# d101-lofi-delay.net
KiCad netlist of a schematic drawn in EAGLE
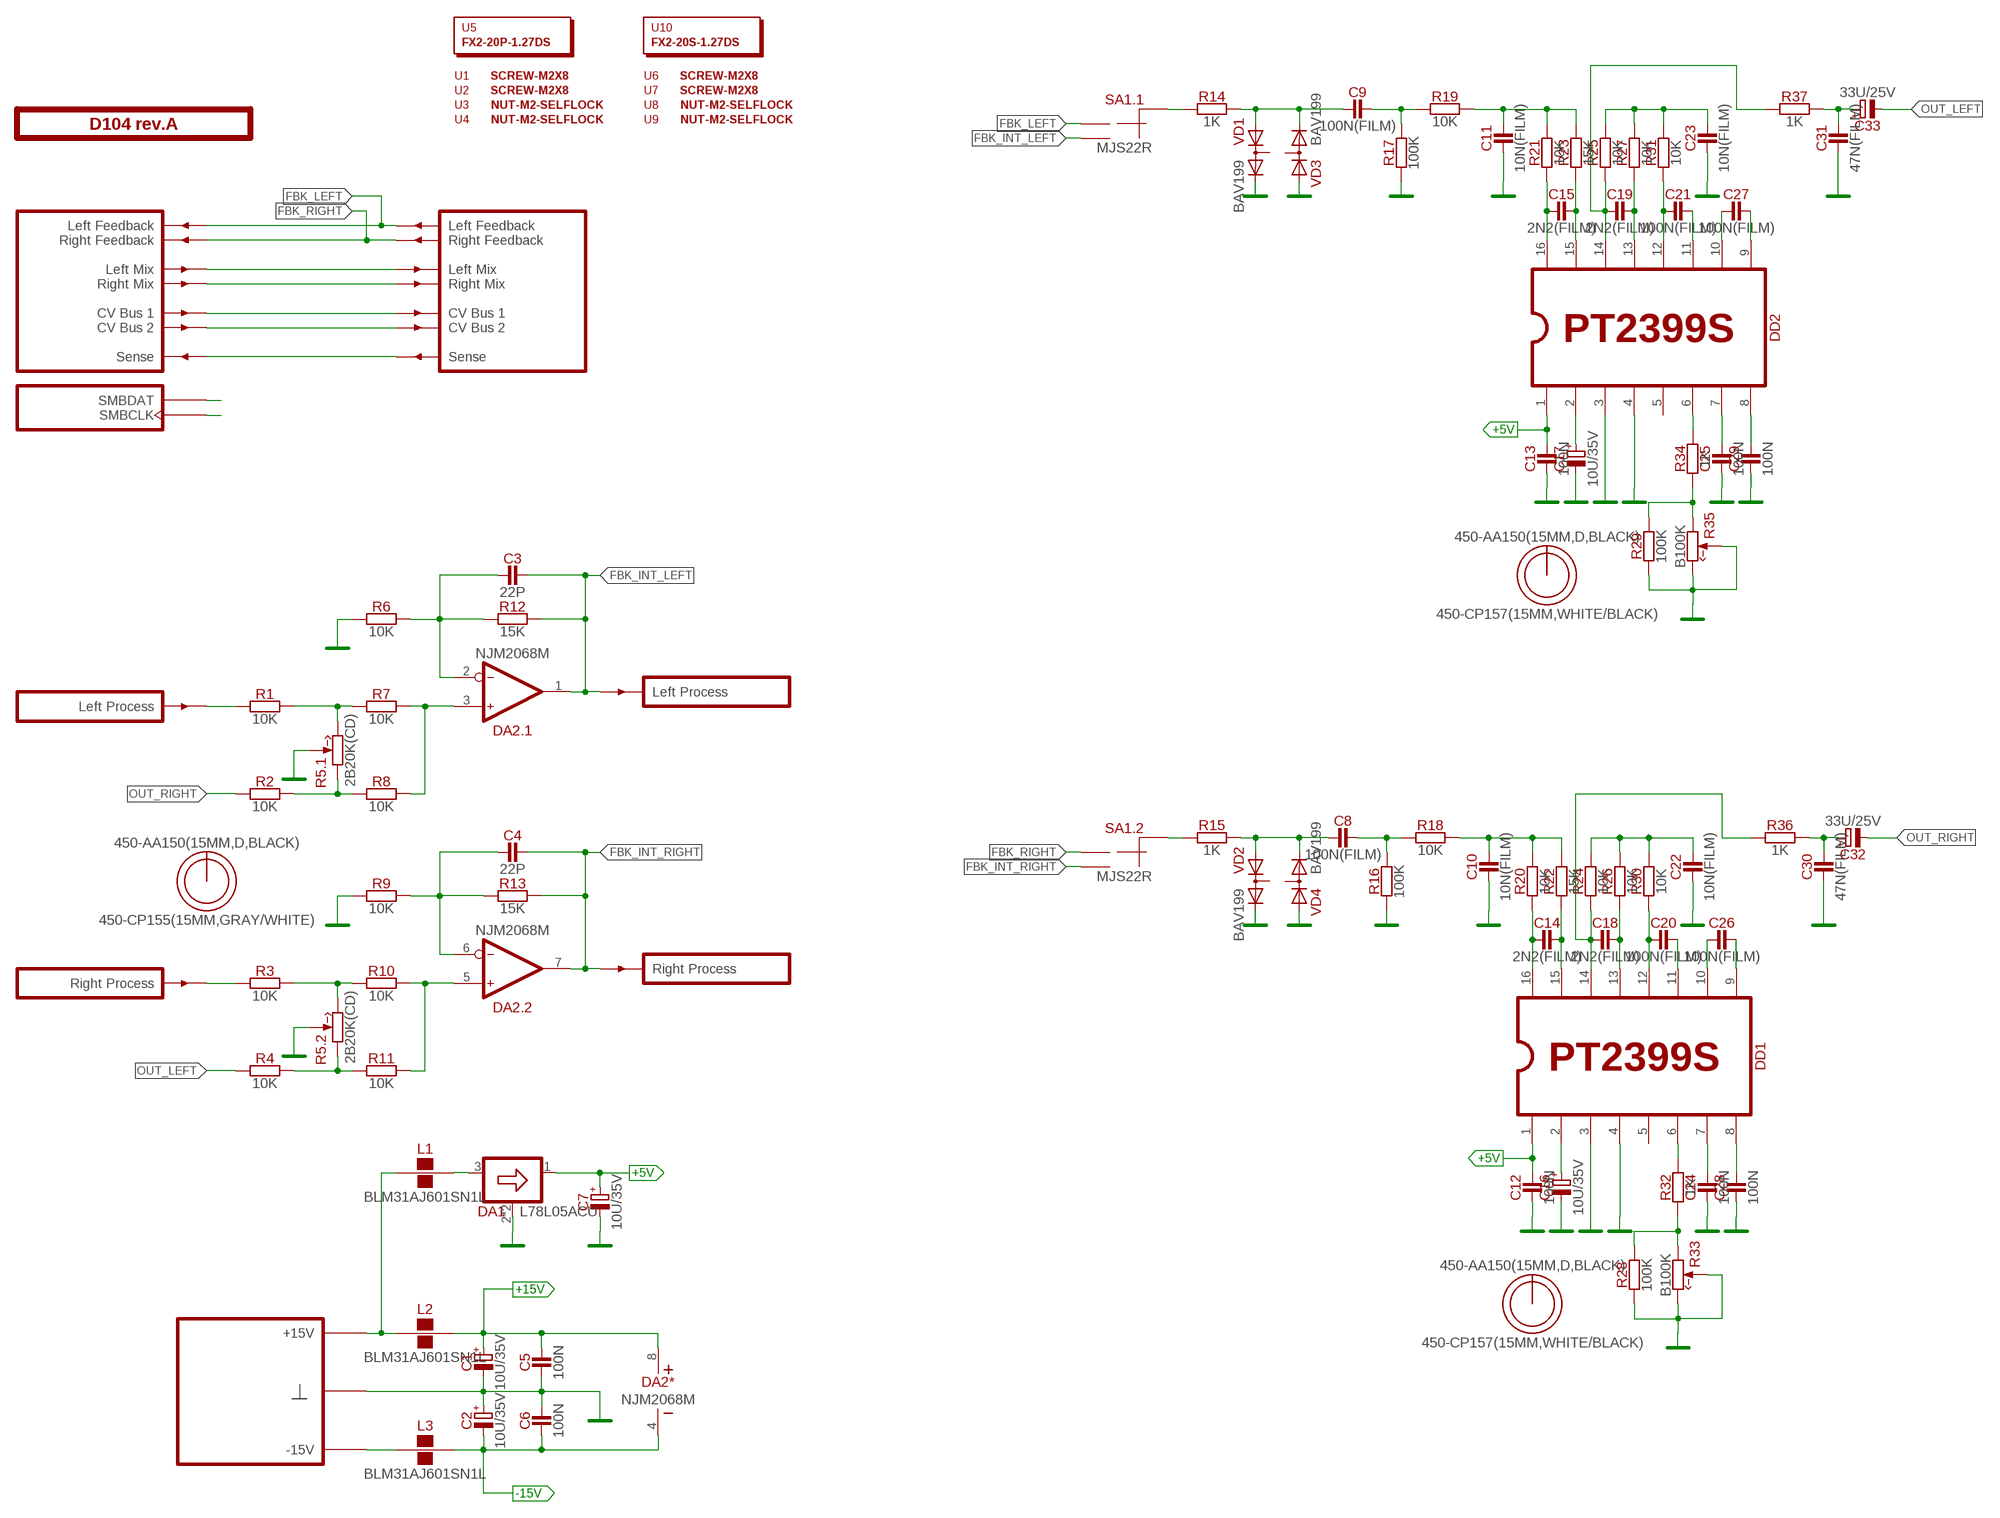
[diagram p0: schematic, sheet 1]

(export (version "E")
  (design (tool "Eeschema 10.0.6"))
  (components
    (comp (ref "C1")
      (value "10U/35V")
      (footprint "eagle-import:E2-5")
      (libsource (lib "eagle-import") (part "?10U/35V"))
    )
    (comp (ref "C2")
      (value "10U/35V")
      (footprint "eagle-import:E2-5")
      (libsource (lib "eagle-import") (part "?10U/35V"))
    )
    (comp (ref "C3")
      (value "22P")
      (footprint "eagle-import:C-0805")
      (libsource (lib "eagle-import") (part "?22P"))
    )
    (comp (ref "C4")
      (value "22P")
      (footprint "eagle-import:C-0805")
      (libsource (lib "eagle-import") (part "?22P"))
    )
    (comp (ref "C5")
      (value "100N")
      (footprint "eagle-import:C-0805")
      (libsource (lib "eagle-import") (part "?100N"))
    )
    (comp (ref "C6")
      (value "100N")
      (footprint "eagle-import:C-0805")
      (libsource (lib "eagle-import") (part "?100N"))
    )
    (comp (ref "C7")
      (value "10U/35V")
      (footprint "eagle-import:E2-5")
      (libsource (lib "eagle-import") (part "?10U/35V"))
    )
    (comp (ref "C8")
      (value "100N(FILM)")
      (footprint "eagle-import:C050-025X075")
      (libsource (lib "eagle-import") (part "?100N(FILM)"))
    )
    (comp (ref "C9")
      (value "100N(FILM)")
      (footprint "eagle-import:C050-025X075")
      (libsource (lib "eagle-import") (part "?100N(FILM)"))
    )
    (comp (ref "C10")
      (value "10N(FILM)")
      (footprint "eagle-import:C050-025X075")
      (libsource (lib "eagle-import") (part "?10N(FILM)"))
    )
    (comp (ref "C11")
      (value "10N(FILM)")
      (footprint "eagle-import:C050-025X075")
      (libsource (lib "eagle-import") (part "?10N(FILM)"))
    )
    (comp (ref "C12")
      (value "100N")
      (footprint "eagle-import:C-0805")
      (libsource (lib "eagle-import") (part "?100N"))
    )
    (comp (ref "C13")
      (value "100N")
      (footprint "eagle-import:C-0805")
      (libsource (lib "eagle-import") (part "?100N"))
    )
    (comp (ref "C14")
      (value "2N2(FILM)")
      (footprint "eagle-import:C050-025X075")
      (libsource (lib "eagle-import") (part "?2N2(FILM)"))
    )
    (comp (ref "C15")
      (value "2N2(FILM)")
      (footprint "eagle-import:C050-025X075")
      (libsource (lib "eagle-import") (part "?2N2(FILM)"))
    )
    (comp (ref "C16")
      (value "10U/35V")
      (footprint "eagle-import:E2-5")
      (libsource (lib "eagle-import") (part "?10U/35V"))
    )
    (comp (ref "C17")
      (value "10U/35V")
      (footprint "eagle-import:E2-5")
      (libsource (lib "eagle-import") (part "?10U/35V"))
    )
    (comp (ref "C18")
      (value "2N2(FILM)")
      (footprint "eagle-import:C050-025X075")
      (libsource (lib "eagle-import") (part "?2N2(FILM)"))
    )
    (comp (ref "C19")
      (value "2N2(FILM)")
      (footprint "eagle-import:C050-025X075")
      (libsource (lib "eagle-import") (part "?2N2(FILM)"))
    )
    (comp (ref "C20")
      (value "100N(FILM)")
      (footprint "eagle-import:C050-025X075")
      (libsource (lib "eagle-import") (part "?100N(FILM)"))
    )
    (comp (ref "C21")
      (value "100N(FILM)")
      (footprint "eagle-import:C050-025X075")
      (libsource (lib "eagle-import") (part "?100N(FILM)"))
    )
    (comp (ref "C22")
      (value "10N(FILM)")
      (footprint "eagle-import:C050-025X075")
      (libsource (lib "eagle-import") (part "?10N(FILM)"))
    )
    (comp (ref "C23")
      (value "10N(FILM)")
      (footprint "eagle-import:C050-025X075")
      (libsource (lib "eagle-import") (part "?10N(FILM)"))
    )
    (comp (ref "C24")
      (value "100N")
      (footprint "eagle-import:C-0805")
      (libsource (lib "eagle-import") (part "?100N"))
    )
    (comp (ref "C25")
      (value "100N")
      (footprint "eagle-import:C-0805")
      (libsource (lib "eagle-import") (part "?100N"))
    )
    (comp (ref "C26")
      (value "100N(FILM)")
      (footprint "eagle-import:C050-025X075")
      (libsource (lib "eagle-import") (part "?100N(FILM)"))
    )
    (comp (ref "C27")
      (value "100N(FILM)")
      (footprint "eagle-import:C050-025X075")
      (libsource (lib "eagle-import") (part "?100N(FILM)"))
    )
    (comp (ref "C28")
      (value "100N")
      (footprint "eagle-import:C-0805")
      (libsource (lib "eagle-import") (part "?100N"))
    )
    (comp (ref "C29")
      (value "100N")
      (footprint "eagle-import:C-0805")
      (libsource (lib "eagle-import") (part "?100N"))
    )
    (comp (ref "C30")
      (value "47N(FILM)")
      (footprint "eagle-import:C050-025X075")
      (libsource (lib "eagle-import") (part "?47N(FILM)"))
    )
    (comp (ref "C31")
      (value "47N(FILM)")
      (footprint "eagle-import:C050-025X075")
      (libsource (lib "eagle-import") (part "?47N(FILM)"))
    )
    (comp (ref "C32")
      (value "33U/25V")
      (footprint "eagle-import:E2,5-7")
      (libsource (lib "eagle-import") (part "?33U/25V"))
    )
    (comp (ref "C33")
      (value "33U/25V")
      (footprint "eagle-import:E2,5-7")
      (libsource (lib "eagle-import") (part "?33U/25V"))
    )
    (comp (ref "DA1")
      (value "L78L05ACU")
      (footprint "eagle-import:SOT89")
      (libsource (lib "eagle-import") (part "?L78L05ACU"))
    )
    (comp (ref "DA2")
      (value "NJM2068M")
      (footprint "eagle-import:SO-8")
      (libsource (lib "eagle-import") (part "NJM2068M"))
    )
    (comp (ref "DD1")
      (value "PT2399S")
      (footprint "eagle-import:SO-16")
      (libsource (lib "eagle-import") (part "PT2399S"))
    )
    (comp (ref "DD2")
      (value "PT2399S")
      (footprint "eagle-import:SO-16")
      (libsource (lib "eagle-import") (part "PT2399S"))
    )
    (comp (ref "L1")
      (value "BLM31AJ601SN1L")
      (footprint "eagle-import:1206")
      (libsource (lib "eagle-import") (part "BLM31AJ601SN1L"))
    )
    (comp (ref "L2")
      (value "BLM31AJ601SN1L")
      (footprint "eagle-import:1206")
      (libsource (lib "eagle-import") (part "BLM31AJ601SN1L"))
    )
    (comp (ref "L3")
      (value "BLM31AJ601SN1L")
      (footprint "eagle-import:1206")
      (libsource (lib "eagle-import") (part "BLM31AJ601SN1L"))
    )
    (comp (ref "O1")
      (value "450-AA150(15MM,D,BLACK)")
      (footprint "eagle-import:EMPTY")
      (libsource (lib "eagle-import") (part "450-AA?150(15MM,D,BLACK)"))
    )
    (comp (ref "O2")
      (value "450-CP155(15MM,GRAY/WHITE)")
      (footprint "eagle-import:EMPTY")
      (libsource (lib "eagle-import") (part "450-C?P155(15MM,GRAY/WHITE)"))
    )
    (comp (ref "O3")
      (value "450-AA150(15MM,D,BLACK)")
      (footprint "eagle-import:EMPTY")
      (libsource (lib "eagle-import") (part "450-AA?150(15MM,D,BLACK)"))
    )
    (comp (ref "O4")
      (value "450-CP157(15MM,WHITE/BLACK)")
      (footprint "eagle-import:EMPTY")
      (libsource (lib "eagle-import") (part "450-C?P157(15MM,WHITE/BLACK)"))
    )
    (comp (ref "O5")
      (value "450-AA150(15MM,D,BLACK)")
      (footprint "eagle-import:EMPTY")
      (libsource (lib "eagle-import") (part "450-AA?150(15MM,D,BLACK)"))
    )
    (comp (ref "O6")
      (value "450-CP157(15MM,WHITE/BLACK)")
      (footprint "eagle-import:EMPTY")
      (libsource (lib "eagle-import") (part "450-C?P157(15MM,WHITE/BLACK)"))
    )
    (comp (ref "PCB1")
      (value "D104 rev.A")
      (footprint "eagle-import:ST2-BOARD-50")
      (libsource (lib "eagle-import") (part "ST2-BOARD-?50"))
    )
    (comp (ref "R1")
      (value "10K")
      (footprint "eagle-import:R-0805")
      (libsource (lib "eagle-import") (part "?10K"))
    )
    (comp (ref "R2")
      (value "10K")
      (footprint "eagle-import:R-0805")
      (libsource (lib "eagle-import") (part "?10K"))
    )
    (comp (ref "R3")
      (value "10K")
      (footprint "eagle-import:R-0805")
      (libsource (lib "eagle-import") (part "?10K"))
    )
    (comp (ref "R4")
      (value "10K")
      (footprint "eagle-import:R-0805")
      (libsource (lib "eagle-import") (part "?10K"))
    )
    (comp (ref "R5")
      (value "2B20K(CD)")
      (footprint "eagle-import:RV11-DUAL")
      (libsource (lib "eagle-import") (part "2?B20K(CD)"))
    )
    (comp (ref "R6")
      (value "10K")
      (footprint "eagle-import:R-0805")
      (libsource (lib "eagle-import") (part "?10K"))
    )
    (comp (ref "R7")
      (value "10K")
      (footprint "eagle-import:R-0805")
      (libsource (lib "eagle-import") (part "?10K"))
    )
    (comp (ref "R8")
      (value "10K")
      (footprint "eagle-import:R-0805")
      (libsource (lib "eagle-import") (part "?10K"))
    )
    (comp (ref "R9")
      (value "10K")
      (footprint "eagle-import:R-0805")
      (libsource (lib "eagle-import") (part "?10K"))
    )
    (comp (ref "R10")
      (value "10K")
      (footprint "eagle-import:R-0805")
      (libsource (lib "eagle-import") (part "?10K"))
    )
    (comp (ref "R11")
      (value "10K")
      (footprint "eagle-import:R-0805")
      (libsource (lib "eagle-import") (part "?10K"))
    )
    (comp (ref "R12")
      (value "15K")
      (footprint "eagle-import:R-0805")
      (libsource (lib "eagle-import") (part "?15K"))
    )
    (comp (ref "R13")
      (value "15K")
      (footprint "eagle-import:R-0805")
      (libsource (lib "eagle-import") (part "?15K"))
    )
    (comp (ref "R14")
      (value "1K")
      (footprint "eagle-import:R-0805")
      (libsource (lib "eagle-import") (part "?1K"))
    )
    (comp (ref "R15")
      (value "1K")
      (footprint "eagle-import:R-0805")
      (libsource (lib "eagle-import") (part "?1K"))
    )
    (comp (ref "R16")
      (value "100K")
      (footprint "eagle-import:R-0805")
      (libsource (lib "eagle-import") (part "?100K"))
    )
    (comp (ref "R17")
      (value "100K")
      (footprint "eagle-import:R-0805")
      (libsource (lib "eagle-import") (part "?100K"))
    )
    (comp (ref "R18")
      (value "10K")
      (footprint "eagle-import:R-0805")
      (libsource (lib "eagle-import") (part "?10K"))
    )
    (comp (ref "R19")
      (value "10K")
      (footprint "eagle-import:R-0805")
      (libsource (lib "eagle-import") (part "?10K"))
    )
    (comp (ref "R20")
      (value "10K")
      (footprint "eagle-import:R-0805")
      (libsource (lib "eagle-import") (part "?10K"))
    )
    (comp (ref "R21")
      (value "10K")
      (footprint "eagle-import:R-0805")
      (libsource (lib "eagle-import") (part "?10K"))
    )
    (comp (ref "R22")
      (value "15K")
      (footprint "eagle-import:R-0805")
      (libsource (lib "eagle-import") (part "?15K"))
    )
    (comp (ref "R23")
      (value "15K")
      (footprint "eagle-import:R-0805")
      (libsource (lib "eagle-import") (part "?15K"))
    )
    (comp (ref "R24")
      (value "10K")
      (footprint "eagle-import:R-0805")
      (libsource (lib "eagle-import") (part "?10K"))
    )
    (comp (ref "R25")
      (value "10K")
      (footprint "eagle-import:R-0805")
      (libsource (lib "eagle-import") (part "?10K"))
    )
    (comp (ref "R26")
      (value "10K")
      (footprint "eagle-import:R-0805")
      (libsource (lib "eagle-import") (part "?10K"))
    )
    (comp (ref "R27")
      (value "10K")
      (footprint "eagle-import:R-0805")
      (libsource (lib "eagle-import") (part "?10K"))
    )
    (comp (ref "R28")
      (value "100K")
      (footprint "eagle-import:R-0805")
      (libsource (lib "eagle-import") (part "?100K"))
    )
    (comp (ref "R29")
      (value "100K")
      (footprint "eagle-import:R-0805")
      (libsource (lib "eagle-import") (part "?100K"))
    )
    (comp (ref "R30")
      (value "10K")
      (footprint "eagle-import:R-0805")
      (libsource (lib "eagle-import") (part "?10K"))
    )
    (comp (ref "R31")
      (value "10K")
      (footprint "eagle-import:R-0805")
      (libsource (lib "eagle-import") (part "?10K"))
    )
    (comp (ref "R32")
      (value "1K")
      (footprint "eagle-import:R-0805")
      (libsource (lib "eagle-import") (part "?1K"))
    )
    (comp (ref "R33")
      (value "B100K")
      (footprint "eagle-import:RV11-SINGLE")
      (libsource (lib "eagle-import") (part "?B100K"))
    )
    (comp (ref "R34")
      (value "1K")
      (footprint "eagle-import:R-0805")
      (libsource (lib "eagle-import") (part "?1K"))
    )
    (comp (ref "R35")
      (value "B100K")
      (footprint "eagle-import:RV11-SINGLE")
      (libsource (lib "eagle-import") (part "?B100K"))
    )
    (comp (ref "R36")
      (value "1K")
      (footprint "eagle-import:R-0805")
      (libsource (lib "eagle-import") (part "?1K"))
    )
    (comp (ref "R37")
      (value "1K")
      (footprint "eagle-import:R-0805")
      (libsource (lib "eagle-import") (part "?1K"))
    )
    (comp (ref "SA1")
      (value "MJS22R")
      (footprint "eagle-import:APEM-MJS22R")
      (libsource (lib "eagle-import") (part "MJS22R"))
    )
    (comp (ref "U1")
      (value "SCREW-M2X8")
      (footprint "eagle-import:EMPTY")
      (libsource (lib "eagle-import") (part "?SCREW-M2X8"))
    )
    (comp (ref "U2")
      (value "SCREW-M2X8")
      (footprint "eagle-import:EMPTY")
      (libsource (lib "eagle-import") (part "?SCREW-M2X8"))
    )
    (comp (ref "U3")
      (value "NUT-M2-SELFLOCK")
      (footprint "eagle-import:EMPTY")
      (libsource (lib "eagle-import") (part "?NUT-M2-SELFLOCK"))
    )
    (comp (ref "U4")
      (value "NUT-M2-SELFLOCK")
      (footprint "eagle-import:EMPTY")
      (libsource (lib "eagle-import") (part "?NUT-M2-SELFLOCK"))
    )
    (comp (ref "U5")
      (value "FX2-20P-1.27DS")
      (footprint "eagle-import:EMPTY")
      (libsource (lib "eagle-import") (part "?FX2-20P-1.27DS"))
    )
    (comp (ref "U6")
      (value "SCREW-M2X8")
      (footprint "eagle-import:EMPTY")
      (libsource (lib "eagle-import") (part "?SCREW-M2X8"))
    )
    (comp (ref "U7")
      (value "SCREW-M2X8")
      (footprint "eagle-import:EMPTY")
      (libsource (lib "eagle-import") (part "?SCREW-M2X8"))
    )
    (comp (ref "U8")
      (value "NUT-M2-SELFLOCK")
      (footprint "eagle-import:EMPTY")
      (libsource (lib "eagle-import") (part "?NUT-M2-SELFLOCK"))
    )
    (comp (ref "U9")
      (value "NUT-M2-SELFLOCK")
      (footprint "eagle-import:EMPTY")
      (libsource (lib "eagle-import") (part "?NUT-M2-SELFLOCK"))
    )
    (comp (ref "U10")
      (value "FX2-20S-1.27DS")
      (footprint "eagle-import:EMPTY")
      (libsource (lib "eagle-import") (part "?FX2-20S-1.27DS"))
    )
    (comp (ref "VD1")
      (value "BAV199")
      (footprint "eagle-import:SOT23")
      (libsource (lib "eagle-import") (part "BAV199"))
    )
    (comp (ref "VD2")
      (value "BAV199")
      (footprint "eagle-import:SOT23")
      (libsource (lib "eagle-import") (part "BAV199"))
    )
    (comp (ref "VD3")
      (value "BAV199")
      (footprint "eagle-import:SOT23")
      (libsource (lib "eagle-import") (part "BAV199"))
    )
    (comp (ref "VD4")
      (value "BAV199")
      (footprint "eagle-import:SOT23")
      (libsource (lib "eagle-import") (part "BAV199"))
    )
  )
  (nets
    (net (code "1") (name "+5V") (class "Default")
      (node (ref "C12") (pin "2") (pinfunction "2_2") (pintype "passive"))
      (node (ref "C13") (pin "2") (pinfunction "2_2") (pintype "passive"))
      (node (ref "C7") (pin "+") (pinfunction "+_+") (pintype "passive"))
      (node (ref "DA1") (pin "1") (pinfunction "OUT_1") (pintype "power_in"))
      (node (ref "DD1") (pin "1") (pinfunction "1_1") (pintype "bidirectional"))
      (node (ref "DD2") (pin "1") (pinfunction "1_1") (pintype "bidirectional"))
    )
    (net (code "2") (name "+15V") (class "Default")
      (node (ref "C1") (pin "+") (pinfunction "+_+") (pintype "passive"))
      (node (ref "C5") (pin "2") (pinfunction "2_2") (pintype "passive"))
      (node (ref "DA2") (pin "8") (pinfunction "V+_8") (pintype "power_in"))
      (node (ref "L2") (pin "2") (pinfunction "2_2") (pintype "passive"))
    )
    (net (code "3") (name "-15V") (class "Default")
      (node (ref "C2") (pin "-") (pinfunction "-_-") (pintype "passive"))
      (node (ref "C6") (pin "1") (pinfunction "1_1") (pintype "passive"))
      (node (ref "DA2") (pin "4") (pinfunction "V-_4") (pintype "power_in"))
      (node (ref "L3") (pin "2") (pinfunction "2_2") (pintype "passive"))
    )
    (net (code "4") (name "FBK_INT_LEFT") (class "Default")
      (node (ref "C3") (pin "2") (pinfunction "2_2") (pintype "passive"))
      (node (ref "DA2") (pin "1") (pinfunction "OUT_1") (pintype "output"))
      (node (ref "PCB1") (pin "BOUTL'") (pinfunction "OUTL_BOUTL'") (pintype "bidirectional"))
      (node (ref "R12") (pin "2") (pinfunction "2_2") (pintype "passive"))
      (node (ref "SA1") (pin "NO1") (pinfunction "2_NO1") (pintype "passive"))
    )
    (net (code "5") (name "FBK_INT_RIGHT") (class "Default")
      (node (ref "C4") (pin "2") (pinfunction "2_2") (pintype "passive"))
      (node (ref "DA2") (pin "7") (pinfunction "OUT_7") (pintype "output"))
      (node (ref "PCB1") (pin "BOUTR'") (pinfunction "OUTR_BOUTR'") (pintype "bidirectional"))
      (node (ref "R13") (pin "2") (pinfunction "2_2") (pintype "passive"))
      (node (ref "SA1") (pin "NO2") (pinfunction "2_NO2") (pintype "passive"))
    )
    (net (code "6") (name "FBK_LEFT") (class "Default")
      (node (ref "PCB1") (pin "ALFBK") (pinfunction "LFBK_ALFBK") (pintype "bidirectional"))
      (node (ref "PCB1") (pin "ALFBK'") (pinfunction "LFBK'_ALFBK'") (pintype "bidirectional"))
      (node (ref "SA1") (pin "NC1") (pinfunction "1_NC1") (pintype "passive"))
    )
    (net (code "7") (name "FBK_RIGHT") (class "Default")
      (node (ref "PCB1") (pin "ARFBK") (pinfunction "RFBK_ARFBK") (pintype "bidirectional"))
      (node (ref "PCB1") (pin "ARFBK'") (pinfunction "RFBK'_ARFBK'") (pintype "bidirectional"))
      (node (ref "SA1") (pin "NC2") (pinfunction "1_NC2") (pintype "passive"))
    )
    (net (code "8") (name "GND") (class "Default")
      (node (ref "C1") (pin "-") (pinfunction "-_-") (pintype "passive"))
      (node (ref "C10") (pin "1") (pinfunction "1_1") (pintype "passive"))
      (node (ref "C11") (pin "1") (pinfunction "1_1") (pintype "passive"))
      (node (ref "C12") (pin "1") (pinfunction "1_1") (pintype "passive"))
      (node (ref "C13") (pin "1") (pinfunction "1_1") (pintype "passive"))
      (node (ref "C16") (pin "-") (pinfunction "-_-") (pintype "passive"))
      (node (ref "C17") (pin "-") (pinfunction "-_-") (pintype "passive"))
      (node (ref "C2") (pin "+") (pinfunction "+_+") (pintype "passive"))
      (node (ref "C22") (pin "1") (pinfunction "1_1") (pintype "passive"))
      (node (ref "C23") (pin "1") (pinfunction "1_1") (pintype "passive"))
      (node (ref "C24") (pin "1") (pinfunction "1_1") (pintype "passive"))
      (node (ref "C25") (pin "1") (pinfunction "1_1") (pintype "passive"))
      (node (ref "C28") (pin "1") (pinfunction "1_1") (pintype "passive"))
      (node (ref "C29") (pin "1") (pinfunction "1_1") (pintype "passive"))
      (node (ref "C30") (pin "1") (pinfunction "1_1") (pintype "passive"))
      (node (ref "C31") (pin "1") (pinfunction "1_1") (pintype "passive"))
      (node (ref "C5") (pin "1") (pinfunction "1_1") (pintype "passive"))
      (node (ref "C6") (pin "2") (pinfunction "2_2") (pintype "passive"))
      (node (ref "C7") (pin "-") (pinfunction "-_-") (pintype "passive"))
      (node (ref "DA1") (pin "2") (pinfunction "GND_2") (pintype "power_in"))
      (node (ref "DA1") (pin "2@1") (pinfunction "GND_2@1") (pintype "power_in"))
      (node (ref "DD1") (pin "3") (pinfunction "3_3") (pintype "bidirectional"))
      (node (ref "DD1") (pin "4") (pinfunction "4_4") (pintype "bidirectional"))
      (node (ref "DD2") (pin "3") (pinfunction "3_3") (pintype "bidirectional"))
      (node (ref "DD2") (pin "4") (pinfunction "4_4") (pintype "bidirectional"))
      (node (ref "PCB1") (pin "B4") (pinfunction "GND_B4") (pintype "bidirectional"))
      (node (ref "PCB1") (pin "B4'") (pinfunction "GND_B4'") (pintype "bidirectional"))
      (node (ref "PCB1") (pin "B5") (pinfunction "GND_B5") (pintype "bidirectional"))
      (node (ref "PCB1") (pin "B5'") (pinfunction "GND_B5'") (pintype "bidirectional"))
      (node (ref "PCB1") (pin "B6") (pinfunction "GND_B6") (pintype "bidirectional"))
      (node (ref "PCB1") (pin "B6'") (pinfunction "GND_B6'") (pintype "bidirectional"))
      (node (ref "PCB1") (pin "B7") (pinfunction "GND_B7") (pintype "bidirectional"))
      (node (ref "PCB1") (pin "B7'") (pinfunction "GND_B7'") (pintype "bidirectional"))
      (node (ref "PCB1") (pin "B8") (pinfunction "GND_B8") (pintype "bidirectional"))
      (node (ref "PCB1") (pin "B8'") (pinfunction "GND_B8'") (pintype "bidirectional"))
      (node (ref "R16") (pin "1") (pinfunction "1_1") (pintype "passive"))
      (node (ref "R17") (pin "1") (pinfunction "1_1") (pintype "passive"))
      (node (ref "R28") (pin "1") (pinfunction "1_1") (pintype "passive"))
      (node (ref "R29") (pin "1") (pinfunction "1_1") (pintype "passive"))
      (node (ref "R33") (pin "2") (pinfunction "W_2") (pintype "passive"))
      (node (ref "R33") (pin "3") (pinfunction "CW_3") (pintype "passive"))
      (node (ref "R35") (pin "2") (pinfunction "W_2") (pintype "passive"))
      (node (ref "R35") (pin "3") (pinfunction "CW_3") (pintype "passive"))
      (node (ref "R5") (pin "2") (pinfunction "W_2") (pintype "passive"))
      (node (ref "R5") (pin "2'") (pinfunction "W_2'") (pintype "passive"))
      (node (ref "R6") (pin "1") (pinfunction "1_1") (pintype "passive"))
      (node (ref "R9") (pin "1") (pinfunction "1_1") (pintype "passive"))
      (node (ref "VD1") (pin "2") (pinfunction "C_2") (pintype "passive"))
      (node (ref "VD2") (pin "2") (pinfunction "C_2") (pintype "passive"))
      (node (ref "VD3") (pin "1") (pinfunction "A_1") (pintype "passive"))
      (node (ref "VD4") (pin "1") (pinfunction "A_1") (pintype "passive"))
    )
    (net (code "9") (name "Net-(C8-Pad2)") (class "Default")
      (node (ref "C8") (pin "2") (pinfunction "2_2") (pintype "passive"))
      (node (ref "R16") (pin "2") (pinfunction "2_2") (pintype "passive"))
      (node (ref "R18") (pin "1") (pinfunction "1_1") (pintype "passive"))
    )
    (net (code "10") (name "Net-(C9-Pad2)") (class "Default")
      (node (ref "C9") (pin "2") (pinfunction "2_2") (pintype "passive"))
      (node (ref "R17") (pin "2") (pinfunction "2_2") (pintype "passive"))
      (node (ref "R19") (pin "1") (pinfunction "1_1") (pintype "passive"))
    )
    (net (code "11") (name "Net-(C10-Pad2)") (class "Default")
      (node (ref "C10") (pin "2") (pinfunction "2_2") (pintype "passive"))
      (node (ref "R18") (pin "2") (pinfunction "2_2") (pintype "passive"))
      (node (ref "R20") (pin "2") (pinfunction "2_2") (pintype "passive"))
      (node (ref "R22") (pin "2") (pinfunction "2_2") (pintype "passive"))
    )
    (net (code "12") (name "Net-(C11-Pad2)") (class "Default")
      (node (ref "C11") (pin "2") (pinfunction "2_2") (pintype "passive"))
      (node (ref "R19") (pin "2") (pinfunction "2_2") (pintype "passive"))
      (node (ref "R21") (pin "2") (pinfunction "2_2") (pintype "passive"))
      (node (ref "R23") (pin "2") (pinfunction "2_2") (pintype "passive"))
    )
    (net (code "13") (name "Net-(C14-Pad1)") (class "Default")
      (node (ref "C14") (pin "1") (pinfunction "1_1") (pintype "passive"))
      (node (ref "DD1") (pin "16") (pinfunction "16_16") (pintype "bidirectional"))
      (node (ref "R20") (pin "1") (pinfunction "1_1") (pintype "passive"))
    )
    (net (code "14") (name "Net-(C14-Pad2)") (class "Default")
      (node (ref "C14") (pin "2") (pinfunction "2_2") (pintype "passive"))
      (node (ref "DD1") (pin "15") (pinfunction "15_15") (pintype "bidirectional"))
      (node (ref "R22") (pin "1") (pinfunction "1_1") (pintype "passive"))
    )
    (net (code "15") (name "Net-(C15-Pad1)") (class "Default")
      (node (ref "C15") (pin "1") (pinfunction "1_1") (pintype "passive"))
      (node (ref "DD2") (pin "16") (pinfunction "16_16") (pintype "bidirectional"))
      (node (ref "R21") (pin "1") (pinfunction "1_1") (pintype "passive"))
    )
    (net (code "16") (name "Net-(C15-Pad2)") (class "Default")
      (node (ref "C15") (pin "2") (pinfunction "2_2") (pintype "passive"))
      (node (ref "DD2") (pin "15") (pinfunction "15_15") (pintype "bidirectional"))
      (node (ref "R23") (pin "1") (pinfunction "1_1") (pintype "passive"))
    )
    (net (code "17") (name "Net-(C16-Pad+)") (class "Default")
      (node (ref "C16") (pin "+") (pinfunction "+_+") (pintype "passive"))
      (node (ref "DD1") (pin "2") (pinfunction "2_2") (pintype "bidirectional"))
    )
    (net (code "18") (name "Net-(C17-Pad+)") (class "Default")
      (node (ref "C17") (pin "+") (pinfunction "+_+") (pintype "passive"))
      (node (ref "DD2") (pin "2") (pinfunction "2_2") (pintype "bidirectional"))
    )
    (net (code "19") (name "Net-(C18-Pad1)") (class "Default")
      (node (ref "C18") (pin "1") (pinfunction "1_1") (pintype "passive"))
      (node (ref "DD1") (pin "14") (pinfunction "14_14") (pintype "bidirectional"))
      (node (ref "R24") (pin "1") (pinfunction "1_1") (pintype "passive"))
      (node (ref "R36") (pin "1") (pinfunction "1_1") (pintype "passive"))
    )
    (net (code "20") (name "Net-(C18-Pad2)") (class "Default")
      (node (ref "C18") (pin "2") (pinfunction "2_2") (pintype "passive"))
      (node (ref "DD1") (pin "13") (pinfunction "13_13") (pintype "bidirectional"))
      (node (ref "R26") (pin "1") (pinfunction "1_1") (pintype "passive"))
    )
    (net (code "21") (name "Net-(C19-Pad1)") (class "Default")
      (node (ref "C19") (pin "1") (pinfunction "1_1") (pintype "passive"))
      (node (ref "DD2") (pin "14") (pinfunction "14_14") (pintype "bidirectional"))
      (node (ref "R25") (pin "1") (pinfunction "1_1") (pintype "passive"))
      (node (ref "R37") (pin "1") (pinfunction "1_1") (pintype "passive"))
    )
    (net (code "22") (name "Net-(C19-Pad2)") (class "Default")
      (node (ref "C19") (pin "2") (pinfunction "2_2") (pintype "passive"))
      (node (ref "DD2") (pin "13") (pinfunction "13_13") (pintype "bidirectional"))
      (node (ref "R27") (pin "1") (pinfunction "1_1") (pintype "passive"))
    )
    (net (code "23") (name "Net-(C20-Pad1)") (class "Default")
      (node (ref "C20") (pin "1") (pinfunction "1_1") (pintype "passive"))
      (node (ref "DD1") (pin "12") (pinfunction "12_12") (pintype "bidirectional"))
      (node (ref "R30") (pin "1") (pinfunction "1_1") (pintype "passive"))
    )
    (net (code "24") (name "Net-(C20-Pad2)") (class "Default")
      (node (ref "C20") (pin "2") (pinfunction "2_2") (pintype "passive"))
      (node (ref "DD1") (pin "11") (pinfunction "11_11") (pintype "bidirectional"))
    )
    (net (code "25") (name "Net-(C21-Pad1)") (class "Default")
      (node (ref "C21") (pin "1") (pinfunction "1_1") (pintype "passive"))
      (node (ref "DD2") (pin "12") (pinfunction "12_12") (pintype "bidirectional"))
      (node (ref "R31") (pin "1") (pinfunction "1_1") (pintype "passive"))
    )
    (net (code "26") (name "Net-(C21-Pad2)") (class "Default")
      (node (ref "C21") (pin "2") (pinfunction "2_2") (pintype "passive"))
      (node (ref "DD2") (pin "11") (pinfunction "11_11") (pintype "bidirectional"))
    )
    (net (code "27") (name "Net-(C22-Pad2)") (class "Default")
      (node (ref "C22") (pin "2") (pinfunction "2_2") (pintype "passive"))
      (node (ref "R24") (pin "2") (pinfunction "2_2") (pintype "passive"))
      (node (ref "R26") (pin "2") (pinfunction "2_2") (pintype "passive"))
      (node (ref "R30") (pin "2") (pinfunction "2_2") (pintype "passive"))
    )
    (net (code "28") (name "Net-(C23-Pad2)") (class "Default")
      (node (ref "C23") (pin "2") (pinfunction "2_2") (pintype "passive"))
      (node (ref "R25") (pin "2") (pinfunction "2_2") (pintype "passive"))
      (node (ref "R27") (pin "2") (pinfunction "2_2") (pintype "passive"))
      (node (ref "R31") (pin "2") (pinfunction "2_2") (pintype "passive"))
    )
    (net (code "29") (name "Net-(C24-Pad2)") (class "Default")
      (node (ref "C24") (pin "2") (pinfunction "2_2") (pintype "passive"))
      (node (ref "DD1") (pin "7") (pinfunction "7_7") (pintype "bidirectional"))
    )
    (net (code "30") (name "Net-(C25-Pad2)") (class "Default")
      (node (ref "C25") (pin "2") (pinfunction "2_2") (pintype "passive"))
      (node (ref "DD2") (pin "7") (pinfunction "7_7") (pintype "bidirectional"))
    )
    (net (code "31") (name "Net-(C26-Pad1)") (class "Default")
      (node (ref "C26") (pin "1") (pinfunction "1_1") (pintype "passive"))
      (node (ref "DD1") (pin "10") (pinfunction "10_10") (pintype "bidirectional"))
    )
    (net (code "32") (name "Net-(C26-Pad2)") (class "Default")
      (node (ref "C26") (pin "2") (pinfunction "2_2") (pintype "passive"))
      (node (ref "DD1") (pin "9") (pinfunction "9_9") (pintype "bidirectional"))
    )
    (net (code "33") (name "Net-(C27-Pad1)") (class "Default")
      (node (ref "C27") (pin "1") (pinfunction "1_1") (pintype "passive"))
      (node (ref "DD2") (pin "10") (pinfunction "10_10") (pintype "bidirectional"))
    )
    (net (code "34") (name "Net-(C27-Pad2)") (class "Default")
      (node (ref "C27") (pin "2") (pinfunction "2_2") (pintype "passive"))
      (node (ref "DD2") (pin "9") (pinfunction "9_9") (pintype "bidirectional"))
    )
    (net (code "35") (name "Net-(C28-Pad2)") (class "Default")
      (node (ref "C28") (pin "2") (pinfunction "2_2") (pintype "passive"))
      (node (ref "DD1") (pin "8") (pinfunction "8_8") (pintype "bidirectional"))
    )
    (net (code "36") (name "Net-(C29-Pad2)") (class "Default")
      (node (ref "C29") (pin "2") (pinfunction "2_2") (pintype "passive"))
      (node (ref "DD2") (pin "8") (pinfunction "8_8") (pintype "bidirectional"))
    )
    (net (code "37") (name "Net-(C30-Pad2)") (class "Default")
      (node (ref "C30") (pin "2") (pinfunction "2_2") (pintype "passive"))
      (node (ref "C32") (pin "+") (pinfunction "+_+") (pintype "passive"))
      (node (ref "R36") (pin "2") (pinfunction "2_2") (pintype "passive"))
    )
    (net (code "38") (name "Net-(C31-Pad2)") (class "Default")
      (node (ref "C31") (pin "2") (pinfunction "2_2") (pintype "passive"))
      (node (ref "C33") (pin "+") (pinfunction "+_+") (pintype "passive"))
      (node (ref "R37") (pin "2") (pinfunction "2_2") (pintype "passive"))
    )
    (net (code "39") (name "Net-(DA1-IN)") (class "Default")
      (node (ref "DA1") (pin "3") (pinfunction "IN_3") (pintype "power_in"))
      (node (ref "L1") (pin "2") (pinfunction "2_2") (pintype "passive"))
    )
    (net (code "40") (name "Net-(DA2B-IN+)") (class "Default")
      (node (ref "DA2") (pin "3") (pinfunction "IN+_3") (pintype "input"))
      (node (ref "R7") (pin "2") (pinfunction "2_2") (pintype "passive"))
      (node (ref "R8") (pin "2") (pinfunction "2_2") (pintype "passive"))
    )
    (net (code "41") (name "Net-(DA2B-IN-)") (class "Default")
      (node (ref "C3") (pin "1") (pinfunction "1_1") (pintype "passive"))
      (node (ref "DA2") (pin "2") (pinfunction "IN-_2") (pintype "input"))
      (node (ref "R12") (pin "1") (pinfunction "1_1") (pintype "passive"))
      (node (ref "R6") (pin "2") (pinfunction "2_2") (pintype "passive"))
    )
    (net (code "42") (name "Net-(DA2C-IN+)") (class "Default")
      (node (ref "DA2") (pin "5") (pinfunction "IN+_5") (pintype "input"))
      (node (ref "R10") (pin "2") (pinfunction "2_2") (pintype "passive"))
      (node (ref "R11") (pin "2") (pinfunction "2_2") (pintype "passive"))
    )
    (net (code "43") (name "Net-(DA2C-IN-)") (class "Default")
      (node (ref "C4") (pin "1") (pinfunction "1_1") (pintype "passive"))
      (node (ref "DA2") (pin "6") (pinfunction "IN-_6") (pintype "input"))
      (node (ref "R13") (pin "1") (pinfunction "1_1") (pintype "passive"))
      (node (ref "R9") (pin "2") (pinfunction "2_2") (pintype "passive"))
    )
    (net (code "44") (name "Net-(DD1-Pad6)") (class "Default")
      (node (ref "DD1") (pin "6") (pinfunction "6_6") (pintype "bidirectional"))
      (node (ref "R32") (pin "2") (pinfunction "2_2") (pintype "passive"))
    )
    (net (code "45") (name "Net-(DD2-Pad6)") (class "Default")
      (node (ref "DD2") (pin "6") (pinfunction "6_6") (pintype "bidirectional"))
      (node (ref "R34") (pin "2") (pinfunction "2_2") (pintype "passive"))
    )
    (net (code "46") (name "Net-(L1-Pad1)") (class "Default")
      (node (ref "L1") (pin "1") (pinfunction "1_1") (pintype "passive"))
      (node (ref "L2") (pin "1") (pinfunction "1_1") (pintype "passive"))
      (node (ref "PCB1") (pin "A+15") (pinfunction "P+15V_A+15") (pintype "bidirectional"))
      (node (ref "PCB1") (pin "A+15'") (pinfunction "P+15V_A+15'") (pintype "bidirectional"))
      (node (ref "PCB1") (pin "B+15") (pinfunction "P+15V_B+15") (pintype "bidirectional"))
      (node (ref "PCB1") (pin "B+15'") (pinfunction "P+15V_B+15'") (pintype "bidirectional"))
    )
    (net (code "47") (name "Net-(L3-Pad1)") (class "Default")
      (node (ref "L3") (pin "1") (pinfunction "1_1") (pintype "passive"))
      (node (ref "PCB1") (pin "A-15") (pinfunction "P-15V_A-15") (pintype "bidirectional"))
      (node (ref "PCB1") (pin "A-15'") (pinfunction "P-15V_A-15'") (pintype "bidirectional"))
      (node (ref "PCB1") (pin "B-15") (pinfunction "P-15V_B-15") (pintype "bidirectional"))
      (node (ref "PCB1") (pin "B-15'") (pinfunction "P-15V_B-15'") (pintype "bidirectional"))
    )
    (net (code "48") (name "Net-(PCB1B-INL)") (class "Default")
      (node (ref "PCB1") (pin "BINL") (pinfunction "INL_BINL") (pintype "bidirectional"))
      (node (ref "R1") (pin "1") (pinfunction "1_1") (pintype "passive"))
    )
    (net (code "49") (name "Net-(PCB1C-INR)") (class "Default")
      (node (ref "PCB1") (pin "BINR") (pinfunction "INR_BINR") (pintype "bidirectional"))
      (node (ref "R3") (pin "1") (pinfunction "1_1") (pintype "passive"))
    )
    (net (code "50") (name "Net-(PCB1F-CV1)") (class "Default")
      (node (ref "PCB1") (pin "ACV1") (pinfunction "CV1_ACV1") (pintype "bidirectional"))
      (node (ref "PCB1") (pin "ACV1'") (pinfunction "CV1'_ACV1'") (pintype "bidirectional"))
    )
    (net (code "51") (name "Net-(PCB1F-CV2)") (class "Default")
      (node (ref "PCB1") (pin "ACV2") (pinfunction "CV2_ACV2") (pintype "bidirectional"))
      (node (ref "PCB1") (pin "ACV2'") (pinfunction "CV2'_ACV2'") (pintype "bidirectional"))
    )
    (net (code "52") (name "Net-(PCB1F-LMIX)") (class "Default")
      (node (ref "PCB1") (pin "ALMIX") (pinfunction "LMIX_ALMIX") (pintype "bidirectional"))
      (node (ref "PCB1") (pin "ALMIX'") (pinfunction "LMIX'_ALMIX'") (pintype "bidirectional"))
    )
    (net (code "53") (name "Net-(PCB1F-RMIX)") (class "Default")
      (node (ref "PCB1") (pin "ARMIX") (pinfunction "RMIX_ARMIX") (pintype "bidirectional"))
      (node (ref "PCB1") (pin "ARMIX'") (pinfunction "RMIX'_ARMIX'") (pintype "bidirectional"))
    )
    (net (code "54") (name "Net-(PCB1F-SENSE)") (class "Default")
      (node (ref "PCB1") (pin "BSENSE") (pinfunction "SENSE_BSENSE") (pintype "bidirectional"))
      (node (ref "PCB1") (pin "BSENSE'") (pinfunction "SENSE'_BSENSE'") (pintype "bidirectional"))
    )
    (net (code "55") (name "Net-(PCB1H-SMBCLK-PadASMBCLK')") (class "Default")
      (node (ref "PCB1") (pin "ASMBCLK") (pinfunction "SMBCLK_ASMBCLK") (pintype "bidirectional"))
      (node (ref "PCB1") (pin "ASMBCLK'") (pinfunction "SMBCLK_ASMBCLK'") (pintype "bidirectional"))
    )
    (net (code "56") (name "Net-(PCB1H-SMBDAT-PadASMBDAT')") (class "Default")
      (node (ref "PCB1") (pin "ASMBDAT") (pinfunction "SMBDAT_ASMBDAT") (pintype "bidirectional"))
      (node (ref "PCB1") (pin "ASMBDAT'") (pinfunction "SMBDAT_ASMBDAT'") (pintype "bidirectional"))
    )
    (net (code "57") (name "Net-(R5A-CCW)") (class "Default")
      (node (ref "R2") (pin "2") (pinfunction "2_2") (pintype "passive"))
      (node (ref "R5") (pin "1") (pinfunction "CCW_1") (pintype "passive"))
      (node (ref "R8") (pin "1") (pinfunction "1_1") (pintype "passive"))
    )
    (net (code "58") (name "Net-(R5A-CW)") (class "Default")
      (node (ref "R1") (pin "2") (pinfunction "2_2") (pintype "passive"))
      (node (ref "R5") (pin "3") (pinfunction "CW_3") (pintype "passive"))
      (node (ref "R7") (pin "1") (pinfunction "1_1") (pintype "passive"))
    )
    (net (code "59") (name "Net-(R5B-CCW)") (class "Default")
      (node (ref "R11") (pin "1") (pinfunction "1_1") (pintype "passive"))
      (node (ref "R4") (pin "2") (pinfunction "2_2") (pintype "passive"))
      (node (ref "R5") (pin "1'") (pinfunction "CCW_1'") (pintype "passive"))
    )
    (net (code "60") (name "Net-(R5B-CW)") (class "Default")
      (node (ref "R10") (pin "1") (pinfunction "1_1") (pintype "passive"))
      (node (ref "R3") (pin "2") (pinfunction "2_2") (pintype "passive"))
      (node (ref "R5") (pin "3'") (pinfunction "CW_3'") (pintype "passive"))
    )
    (net (code "61") (name "Net-(R33-CCW)") (class "Default")
      (node (ref "R28") (pin "2") (pinfunction "2_2") (pintype "passive"))
      (node (ref "R32") (pin "1") (pinfunction "1_1") (pintype "passive"))
      (node (ref "R33") (pin "1") (pinfunction "CCW_1") (pintype "passive"))
    )
    (net (code "62") (name "Net-(R35-CCW)") (class "Default")
      (node (ref "R29") (pin "2") (pinfunction "2_2") (pintype "passive"))
      (node (ref "R34") (pin "1") (pinfunction "1_1") (pintype "passive"))
      (node (ref "R35") (pin "1") (pinfunction "CCW_1") (pintype "passive"))
    )
    (net (code "63") (name "Net-(SA1A-CM)") (class "Default")
      (node (ref "R14") (pin "1") (pinfunction "1_1") (pintype "passive"))
      (node (ref "SA1") (pin "C1") (pinfunction "CM_C1") (pintype "passive"))
    )
    (net (code "64") (name "Net-(SA1B-CM)") (class "Default")
      (node (ref "R15") (pin "1") (pinfunction "1_1") (pintype "passive"))
      (node (ref "SA1") (pin "C2") (pinfunction "CM_C2") (pintype "passive"))
    )
    (net (code "65") (name "Net-(VD1-A)") (class "Default")
      (node (ref "C9") (pin "1") (pinfunction "1_1") (pintype "passive"))
      (node (ref "R14") (pin "2") (pinfunction "2_2") (pintype "passive"))
      (node (ref "VD1") (pin "1") (pinfunction "A_1") (pintype "passive"))
      (node (ref "VD3") (pin "2") (pinfunction "C_2") (pintype "passive"))
    )
    (net (code "66") (name "Net-(VD2-A)") (class "Default")
      (node (ref "C8") (pin "1") (pinfunction "1_1") (pintype "passive"))
      (node (ref "R15") (pin "2") (pinfunction "2_2") (pintype "passive"))
      (node (ref "VD2") (pin "1") (pinfunction "A_1") (pintype "passive"))
      (node (ref "VD4") (pin "2") (pinfunction "C_2") (pintype "passive"))
    )
    (net (code "67") (name "OUT_LEFT") (class "Default")
      (node (ref "C33") (pin "-") (pinfunction "-_-") (pintype "passive"))
      (node (ref "R4") (pin "1") (pinfunction "1_1") (pintype "passive"))
    )
    (net (code "68") (name "OUT_RIGHT") (class "Default")
      (node (ref "C32") (pin "-") (pinfunction "-_-") (pintype "passive"))
      (node (ref "R2") (pin "1") (pinfunction "1_1") (pintype "passive"))
    )
    (net (code "69") (name "unconnected-(DD1-Pad5)") (class "Default")
      (node (ref "DD1") (pin "5") (pinfunction "5_5") (pintype "bidirectional"))
    )
    (net (code "70") (name "unconnected-(DD2-Pad5)") (class "Default")
      (node (ref "DD2") (pin "5") (pinfunction "5_5") (pintype "bidirectional"))
    )
    (net (code "71") (name "unconnected-(VD1-CMN-Pad3)") (class "Default")
      (node (ref "VD1") (pin "3") (pinfunction "CMN_3") (pintype "passive"))
    )
    (net (code "72") (name "unconnected-(VD2-CMN-Pad3)") (class "Default")
      (node (ref "VD2") (pin "3") (pinfunction "CMN_3") (pintype "passive"))
    )
    (net (code "73") (name "unconnected-(VD3-CMN-Pad3)") (class "Default")
      (node (ref "VD3") (pin "3") (pinfunction "CMN_3") (pintype "passive"))
    )
    (net (code "74") (name "unconnected-(VD4-CMN-Pad3)") (class "Default")
      (node (ref "VD4") (pin "3") (pinfunction "CMN_3") (pintype "passive"))
    )
  )
)
